# UP-4_v9.net
KiCad netlist of a schematic drawn in EAGLE
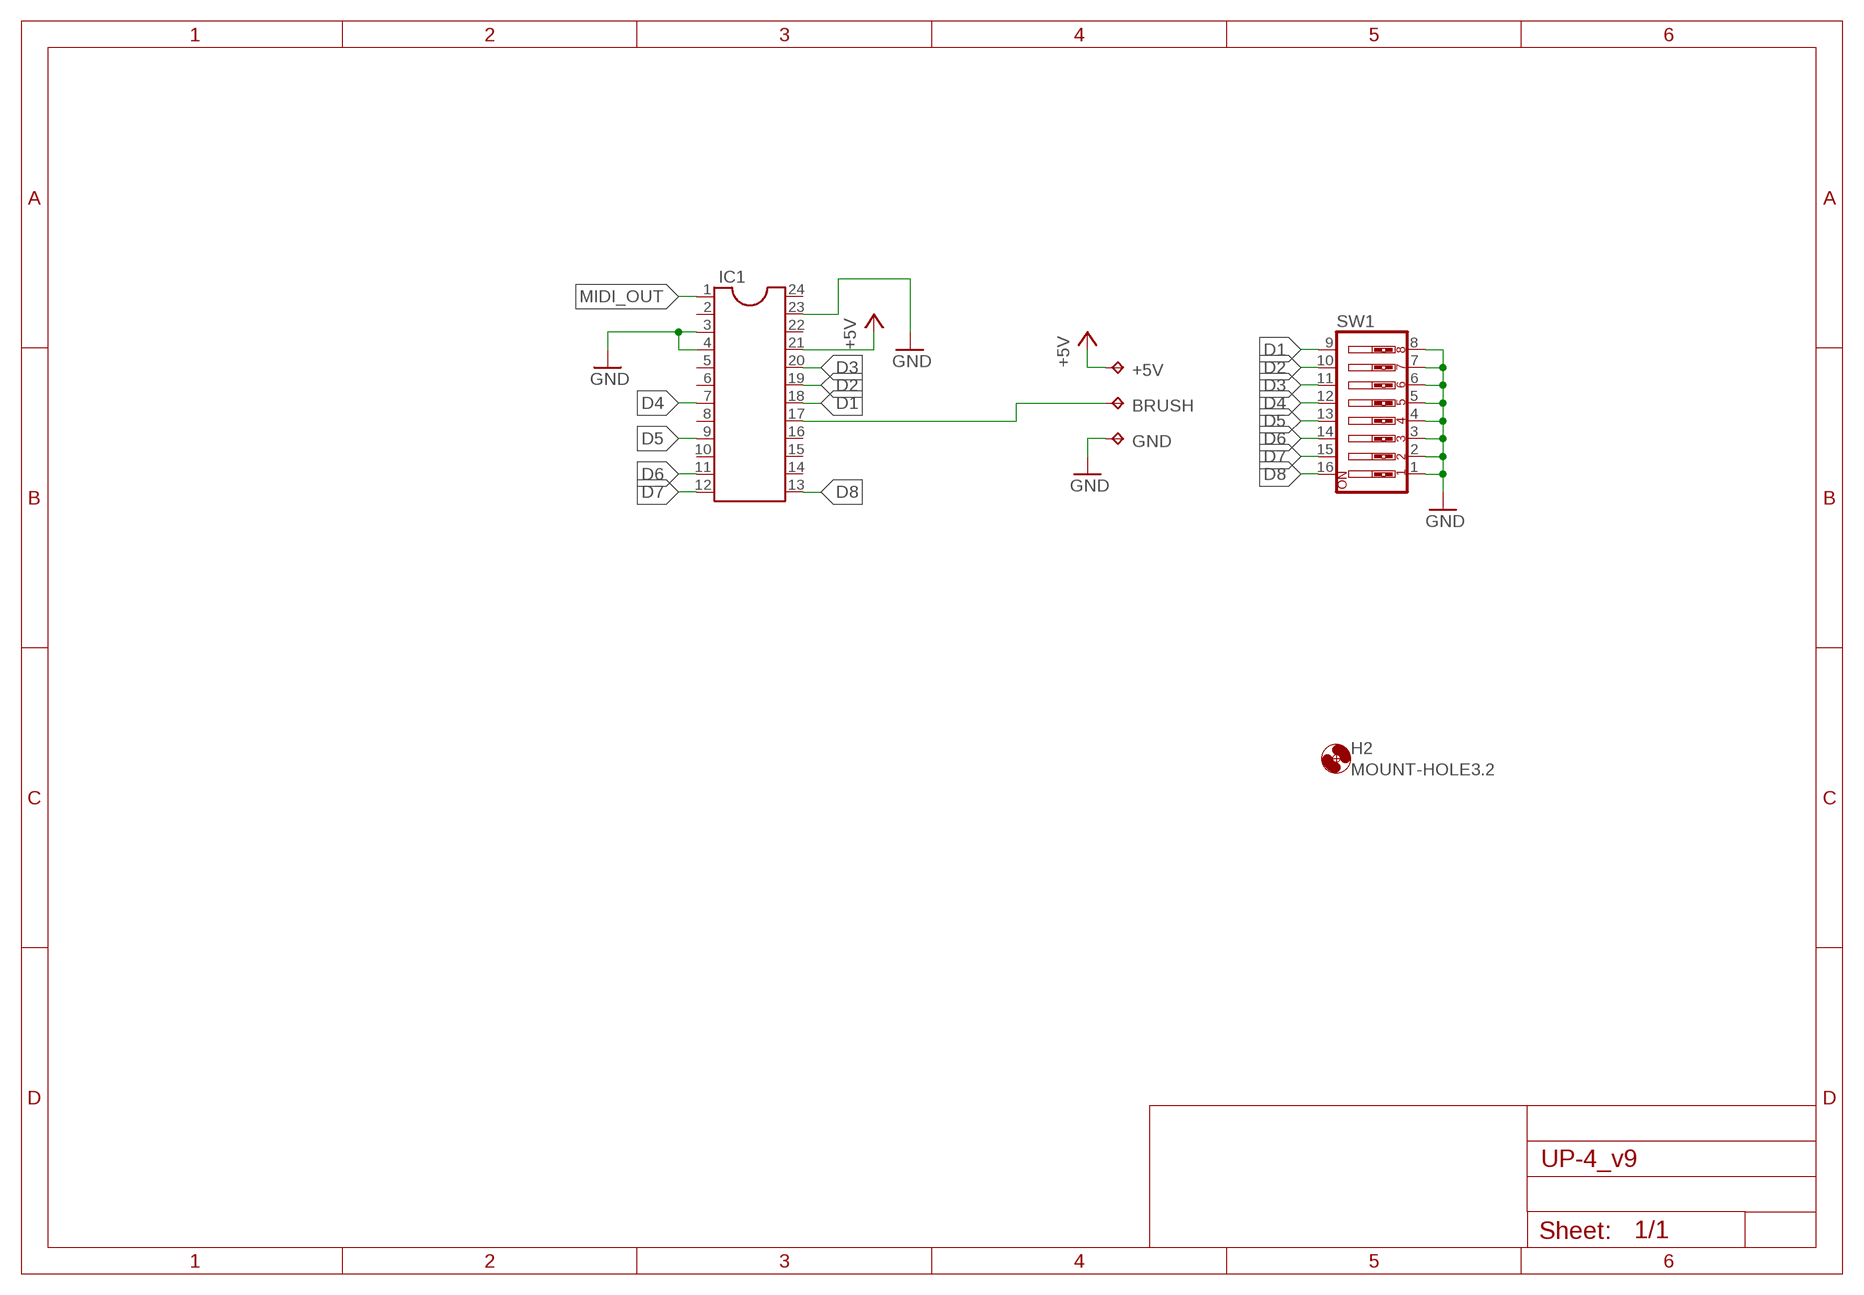
[diagram p0: schematic, sheet 1]

(export (version "E")
  (design (tool "Eeschema 10.0.6"))
  (components
    (comp (ref "+5V")
      (value "TPB2,54")
      (footprint "eagle-import:B2,54")
      (libsource (lib "eagle-import") (part "TPB2,54"))
    )
    (comp (ref "BRUSH")
      (value "TPB2,54")
      (footprint "eagle-import:B2,54")
      (libsource (lib "eagle-import") (part "TPB2,54"))
    )
    (comp (ref "GND")
      (value "TPB2,54")
      (footprint "eagle-import:B2,54")
      (libsource (lib "eagle-import") (part "TPB2,54"))
    )
    (comp (ref "H2")
      (value "MOUNT-HOLE3.2")
      (footprint "eagle-import:3,2")
      (libsource (lib "eagle-import") (part "MOUNT-HOLE3.2"))
    )
    (comp (ref "IC1")
      (value "DIL24-6")
      (footprint "eagle-import:DIL24-6")
      (libsource (lib "eagle-import") (part "DIL24-6"))
    )
    (comp (ref "SW1")
      (value "SW_DIP-8")
      (footprint "eagle-import:EDG-08")
      (libsource (lib "eagle-import") (part "SW_DIP-8"))
    )
  )
  (nets
    (net (code "1") (name "+5V") (class "Default")
      (node (ref "+5V") (pin "TP") (pinfunction "TP_TP") (pintype "input"))
      (node (ref "IC1") (pin "21") (pinfunction "21_21") (pintype "passive"))
    )
    (net (code "2") (name "D1") (class "Default")
      (node (ref "IC1") (pin "18") (pinfunction "18_18") (pintype "passive"))
      (node (ref "SW1") (pin "9") (pinfunction "9_9") (pintype "passive"))
    )
    (net (code "3") (name "D2") (class "Default")
      (node (ref "IC1") (pin "19") (pinfunction "19_19") (pintype "passive"))
      (node (ref "SW1") (pin "10") (pinfunction "10_10") (pintype "passive"))
    )
    (net (code "4") (name "D3") (class "Default")
      (node (ref "IC1") (pin "20") (pinfunction "20_20") (pintype "passive"))
      (node (ref "SW1") (pin "11") (pinfunction "11_11") (pintype "passive"))
    )
    (net (code "5") (name "D4") (class "Default")
      (node (ref "IC1") (pin "7") (pinfunction "7_7") (pintype "passive"))
      (node (ref "SW1") (pin "12") (pinfunction "12_12") (pintype "passive"))
    )
    (net (code "6") (name "D5") (class "Default")
      (node (ref "IC1") (pin "9") (pinfunction "9_9") (pintype "passive"))
      (node (ref "SW1") (pin "13") (pinfunction "13_13") (pintype "passive"))
    )
    (net (code "7") (name "D6") (class "Default")
      (node (ref "IC1") (pin "11") (pinfunction "11_11") (pintype "passive"))
      (node (ref "SW1") (pin "14") (pinfunction "14_14") (pintype "passive"))
    )
    (net (code "8") (name "D7") (class "Default")
      (node (ref "IC1") (pin "12") (pinfunction "12_12") (pintype "passive"))
      (node (ref "SW1") (pin "15") (pinfunction "15_15") (pintype "passive"))
    )
    (net (code "9") (name "D8") (class "Default")
      (node (ref "IC1") (pin "13") (pinfunction "13_13") (pintype "passive"))
      (node (ref "SW1") (pin "16") (pinfunction "16_16") (pintype "passive"))
    )
    (net (code "10") (name "GND") (class "Default")
      (node (ref "GND") (pin "TP") (pinfunction "TP_TP") (pintype "input"))
      (node (ref "IC1") (pin "23") (pinfunction "23_23") (pintype "passive"))
      (node (ref "IC1") (pin "3") (pinfunction "3_3") (pintype "passive"))
      (node (ref "IC1") (pin "4") (pinfunction "4_4") (pintype "passive"))
      (node (ref "SW1") (pin "1") (pinfunction "1_1") (pintype "passive"))
      (node (ref "SW1") (pin "2") (pinfunction "2_2") (pintype "passive"))
      (node (ref "SW1") (pin "3") (pinfunction "3_3") (pintype "passive"))
      (node (ref "SW1") (pin "4") (pinfunction "4_4") (pintype "passive"))
      (node (ref "SW1") (pin "5") (pinfunction "5_5") (pintype "passive"))
      (node (ref "SW1") (pin "6") (pinfunction "6_6") (pintype "passive"))
      (node (ref "SW1") (pin "7") (pinfunction "7_7") (pintype "passive"))
      (node (ref "SW1") (pin "8") (pinfunction "8_8") (pintype "passive"))
    )
    (net (code "11") (name "MIDI_OUT") (class "Default")
      (node (ref "IC1") (pin "1") (pinfunction "1_1") (pintype "passive"))
    )
    (net (code "12") (name "Net-(BRUSH-PadTP)") (class "Default")
      (node (ref "BRUSH") (pin "TP") (pinfunction "TP_TP") (pintype "input"))
      (node (ref "IC1") (pin "17") (pinfunction "17_17") (pintype "passive"))
    )
    (net (code "13") (name "unconnected-(IC1-Pad2)") (class "Default")
      (node (ref "IC1") (pin "2") (pinfunction "2_2") (pintype "passive"))
    )
    (net (code "14") (name "unconnected-(IC1-Pad5)") (class "Default")
      (node (ref "IC1") (pin "5") (pinfunction "5_5") (pintype "passive"))
    )
    (net (code "15") (name "unconnected-(IC1-Pad6)") (class "Default")
      (node (ref "IC1") (pin "6") (pinfunction "6_6") (pintype "passive"))
    )
    (net (code "16") (name "unconnected-(IC1-Pad8)") (class "Default")
      (node (ref "IC1") (pin "8") (pinfunction "8_8") (pintype "passive"))
    )
    (net (code "17") (name "unconnected-(IC1-Pad10)") (class "Default")
      (node (ref "IC1") (pin "10") (pinfunction "10_10") (pintype "passive"))
    )
    (net (code "18") (name "unconnected-(IC1-Pad14)") (class "Default")
      (node (ref "IC1") (pin "14") (pinfunction "14_14") (pintype "passive"))
    )
    (net (code "19") (name "unconnected-(IC1-Pad15)") (class "Default")
      (node (ref "IC1") (pin "15") (pinfunction "15_15") (pintype "passive"))
    )
    (net (code "20") (name "unconnected-(IC1-Pad16)") (class "Default")
      (node (ref "IC1") (pin "16") (pinfunction "16_16") (pintype "passive"))
    )
    (net (code "21") (name "unconnected-(IC1-Pad22)") (class "Default")
      (node (ref "IC1") (pin "22") (pinfunction "22_22") (pintype "passive"))
    )
    (net (code "22") (name "unconnected-(IC1-Pad24)") (class "Default")
      (node (ref "IC1") (pin "24") (pinfunction "24_24") (pintype "passive"))
    )
  )
)
